# keyboard.net
KiCad netlist of a schematic drawn in EasyEDA Pro
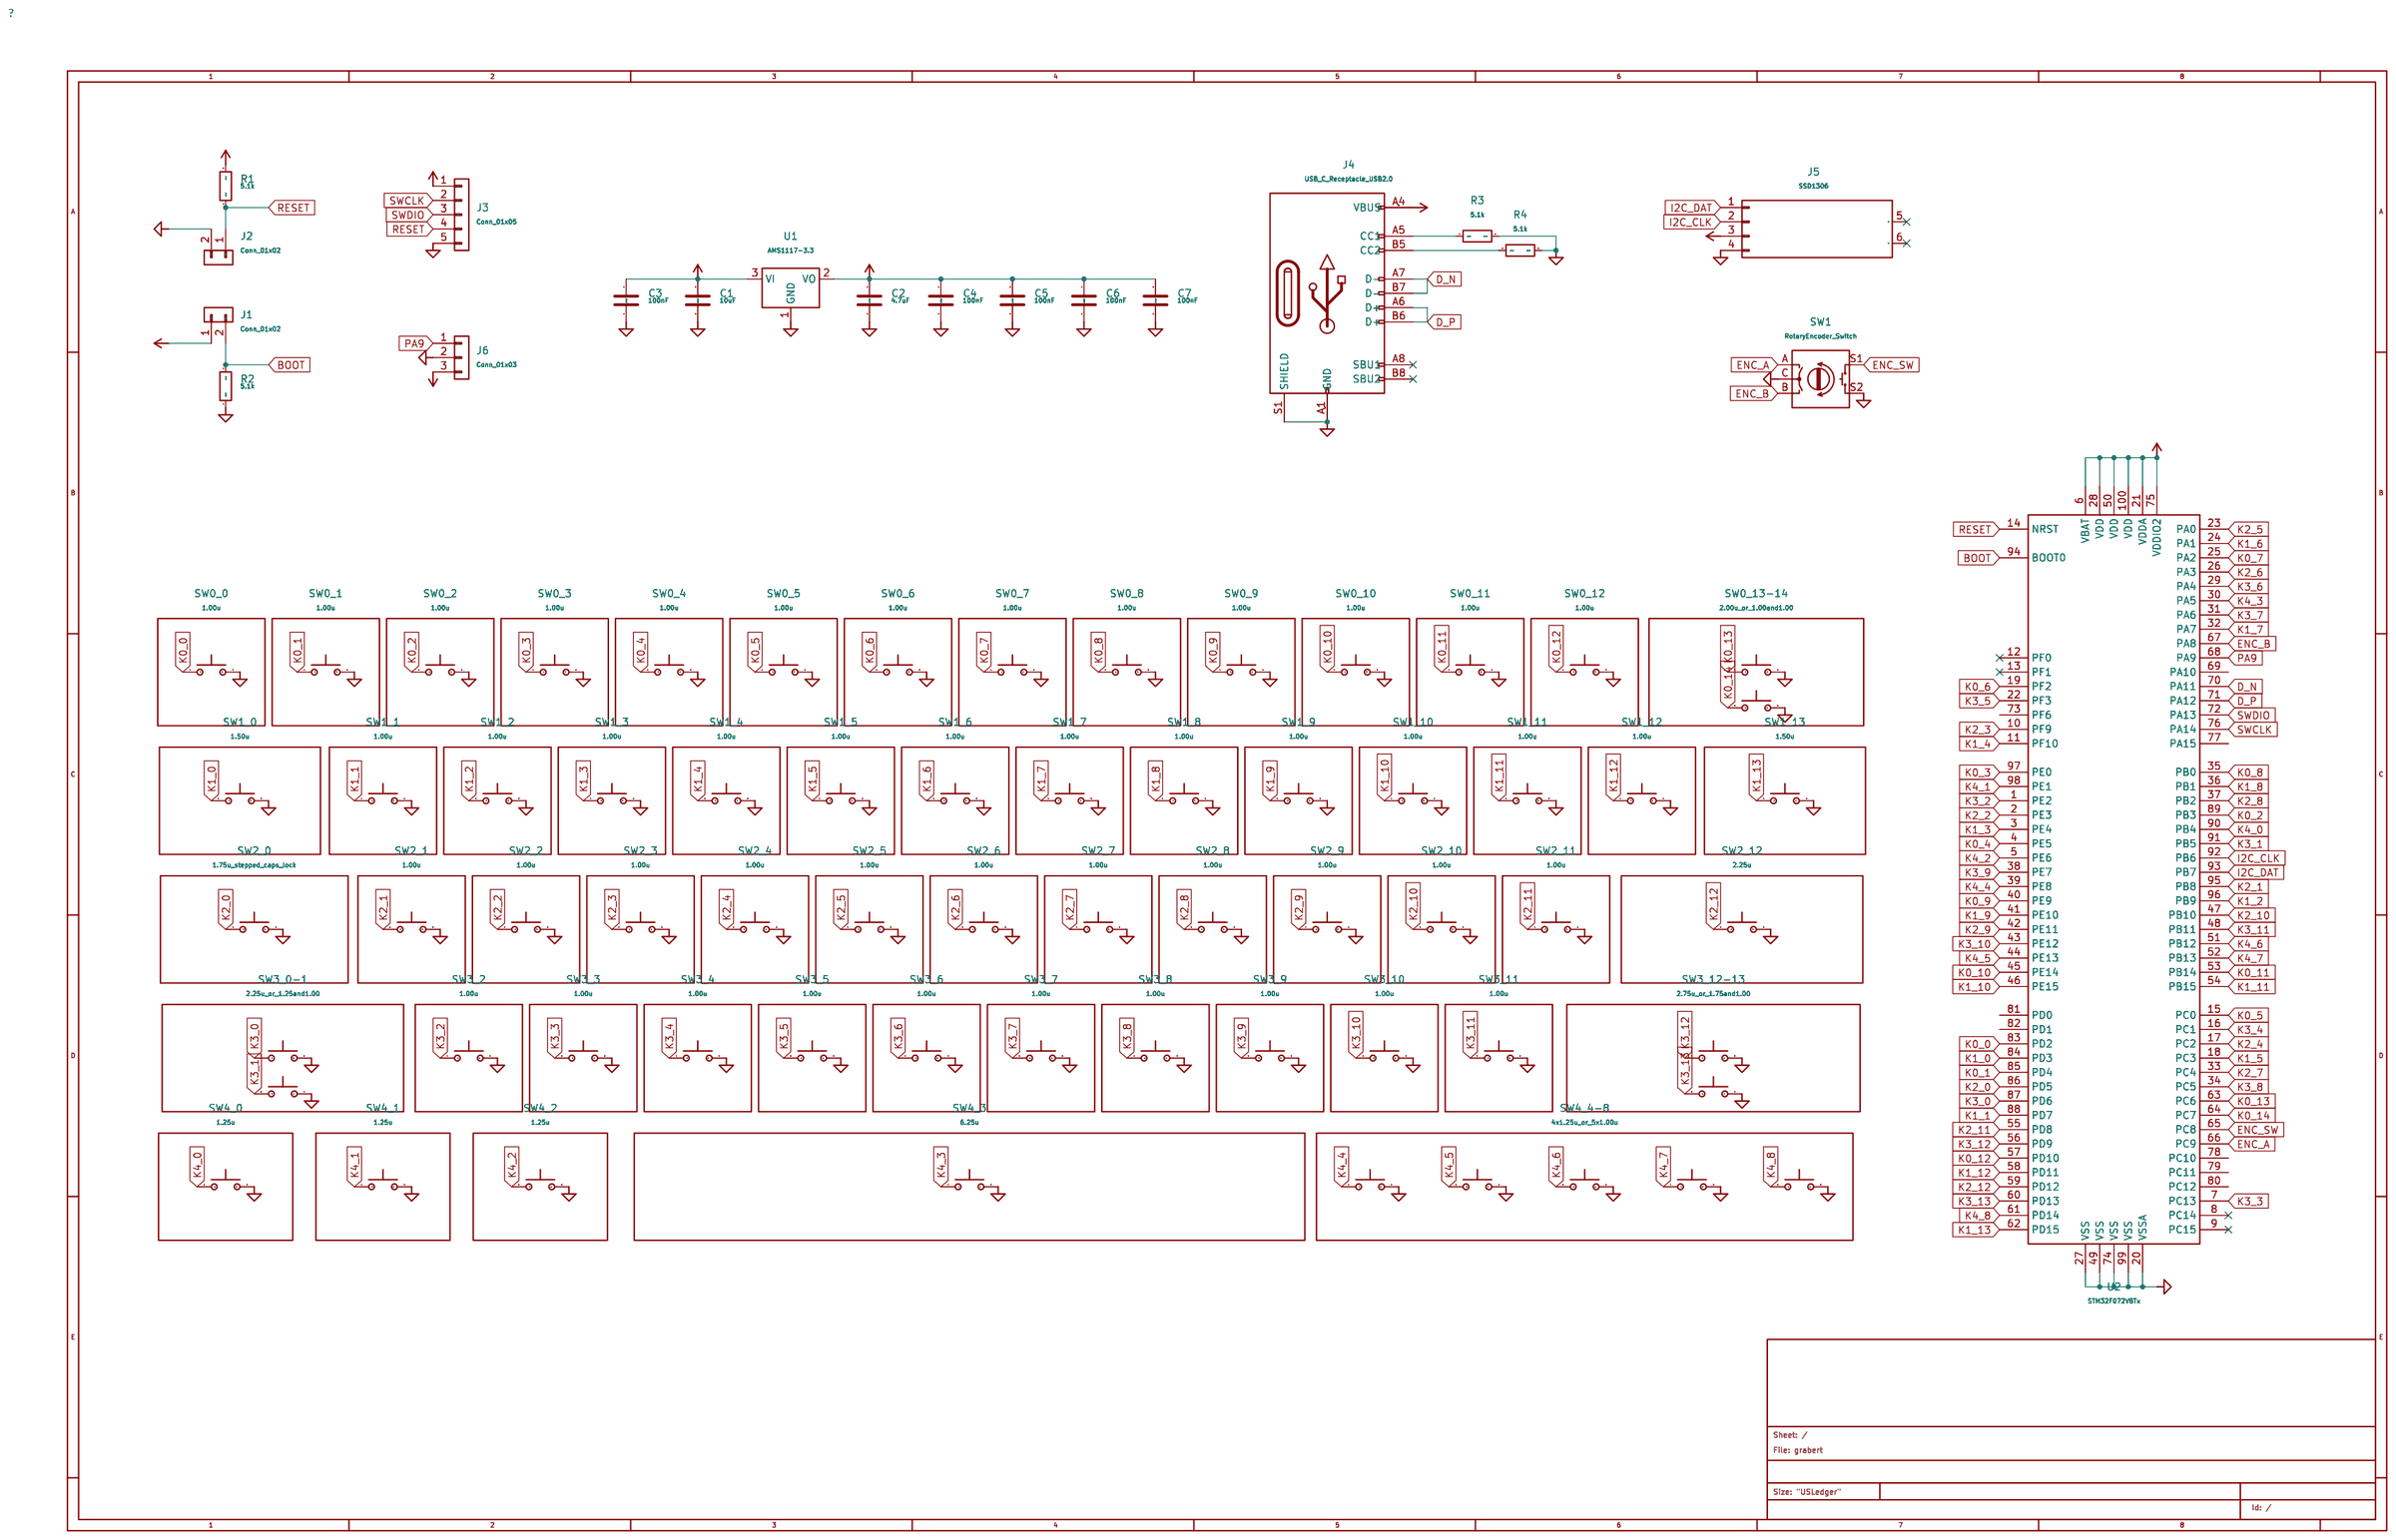
[diagram p0: schematic sheet]

(export (version "E")
  (design (tool "Eeschema 10.0.6"))
  (components
    (comp (ref "C1") (value "10uF") (libsource (lib "easyedapro") (part "Device_C")))
    (comp (ref "C2") (value "4.7uF") (libsource (lib "easyedapro") (part "Device_C")))
    (comp (ref "C3") (value "100nF") (libsource (lib "easyedapro") (part "Device_C")))
    (comp (ref "C4") (value "100nF") (libsource (lib "easyedapro") (part "Device_C")))
    (comp (ref "C5") (value "100nF") (libsource (lib "easyedapro") (part "Device_C")))
    (comp (ref "C6") (value "100nF") (libsource (lib "easyedapro") (part "Device_C")))
    (comp (ref "C7") (value "100nF") (libsource (lib "easyedapro") (part "Device_C")))
    (comp (ref "J1")
      (value "Conn_01x02")
      (libsource (lib "easyedapro") (part "Connector_Generic_Conn_01x02"))
    )
    (comp (ref "J2")
      (value "Conn_01x02")
      (libsource (lib "easyedapro") (part "Connector_Generic_Conn_01x02"))
    )
    (comp (ref "J3")
      (value "Conn_01x05")
      (libsource (lib "easyedapro") (part "Connector_Generic_Conn_01x05"))
    )
    (comp (ref "J4")
      (value "USB_C_Receptacle_USB2.0")
      (libsource (lib "easyedapro") (part "Connector_USB_C_Receptacle_USB2.0"))
    )
    (comp (ref "J5") (value "SSD1306") (libsource (lib "easyedapro") (part "kobuss_SSD1306")))
    (comp (ref "J6")
      (value "Conn_01x03")
      (libsource (lib "easyedapro") (part "Connector_Generic_Conn_01x03"))
    )
    (comp (ref "R1") (value "5.1k") (libsource (lib "easyedapro") (part "Device_R")))
    (comp (ref "R2") (value "5.1k") (libsource (lib "easyedapro") (part "Device_R")))
    (comp (ref "R3") (value "5.1k") (libsource (lib "easyedapro") (part "Device_R")))
    (comp (ref "R4") (value "5.1k") (libsource (lib "easyedapro") (part "Device_R")))
    (comp (ref "SW0_0") (value "1.00u") (libsource (lib "easyedapro") (part "kobuss_1.00u")))
    (comp (ref "SW0_1") (value "1.00u") (libsource (lib "easyedapro") (part "kobuss_1.00u")))
    (comp (ref "SW0_2") (value "1.00u") (libsource (lib "easyedapro") (part "kobuss_1.00u")))
    (comp (ref "SW0_3") (value "1.00u") (libsource (lib "easyedapro") (part "kobuss_1.00u")))
    (comp (ref "SW0_4") (value "1.00u") (libsource (lib "easyedapro") (part "kobuss_1.00u")))
    (comp (ref "SW0_5") (value "1.00u") (libsource (lib "easyedapro") (part "kobuss_1.00u")))
    (comp (ref "SW0_6") (value "1.00u") (libsource (lib "easyedapro") (part "kobuss_1.00u")))
    (comp (ref "SW0_7") (value "1.00u") (libsource (lib "easyedapro") (part "kobuss_1.00u")))
    (comp (ref "SW0_8") (value "1.00u") (libsource (lib "easyedapro") (part "kobuss_1.00u")))
    (comp (ref "SW0_9") (value "1.00u") (libsource (lib "easyedapro") (part "kobuss_1.00u")))
    (comp (ref "SW0_10") (value "1.00u") (libsource (lib "easyedapro") (part "kobuss_1.00u")))
    (comp (ref "SW0_11") (value "1.00u") (libsource (lib "easyedapro") (part "kobuss_1.00u")))
    (comp (ref "SW0_12") (value "1.00u") (libsource (lib "easyedapro") (part "kobuss_1.00u")))
    (comp (ref "SW0_13-14")
      (value "2.00u_or_1.00and1.00")
      (libsource (lib "easyedapro") (part "kobuss_2.00u_or_1.00and1.00"))
    )
    (comp (ref "SW1")
      (value "RotaryEncoder_Switch")
      (libsource (lib "easyedapro") (part "Device_RotaryEncoder_Switch"))
    )
    (comp (ref "SW1_0") (value "1.50u") (libsource (lib "easyedapro") (part "kobuss_1.50u")))
    (comp (ref "SW1_1") (value "1.00u") (libsource (lib "easyedapro") (part "kobuss_1.00u")))
    (comp (ref "SW1_2") (value "1.00u") (libsource (lib "easyedapro") (part "kobuss_1.00u")))
    (comp (ref "SW1_3") (value "1.00u") (libsource (lib "easyedapro") (part "kobuss_1.00u")))
    (comp (ref "SW1_4") (value "1.00u") (libsource (lib "easyedapro") (part "kobuss_1.00u")))
    (comp (ref "SW1_5") (value "1.00u") (libsource (lib "easyedapro") (part "kobuss_1.00u")))
    (comp (ref "SW1_6") (value "1.00u") (libsource (lib "easyedapro") (part "kobuss_1.00u")))
    (comp (ref "SW1_7") (value "1.00u") (libsource (lib "easyedapro") (part "kobuss_1.00u")))
    (comp (ref "SW1_8") (value "1.00u") (libsource (lib "easyedapro") (part "kobuss_1.00u")))
    (comp (ref "SW1_9") (value "1.00u") (libsource (lib "easyedapro") (part "kobuss_1.00u")))
    (comp (ref "SW1_10") (value "1.00u") (libsource (lib "easyedapro") (part "kobuss_1.00u")))
    (comp (ref "SW1_11") (value "1.00u") (libsource (lib "easyedapro") (part "kobuss_1.00u")))
    (comp (ref "SW1_12") (value "1.00u") (libsource (lib "easyedapro") (part "kobuss_1.00u")))
    (comp (ref "SW1_13") (value "1.50u") (libsource (lib "easyedapro") (part "kobuss_1.50u")))
    (comp (ref "SW2_0")
      (value "1.75u_stepped_caps_lock")
      (libsource (lib "easyedapro") (part "kobuss_1.75u_stepped_caps_lock"))
    )
    (comp (ref "SW2_1") (value "1.00u") (libsource (lib "easyedapro") (part "kobuss_1.00u")))
    (comp (ref "SW2_2") (value "1.00u") (libsource (lib "easyedapro") (part "kobuss_1.00u")))
    (comp (ref "SW2_3") (value "1.00u") (libsource (lib "easyedapro") (part "kobuss_1.00u")))
    (comp (ref "SW2_4") (value "1.00u") (libsource (lib "easyedapro") (part "kobuss_1.00u")))
    (comp (ref "SW2_5") (value "1.00u") (libsource (lib "easyedapro") (part "kobuss_1.00u")))
    (comp (ref "SW2_6") (value "1.00u") (libsource (lib "easyedapro") (part "kobuss_1.00u")))
    (comp (ref "SW2_7") (value "1.00u") (libsource (lib "easyedapro") (part "kobuss_1.00u")))
    (comp (ref "SW2_8") (value "1.00u") (libsource (lib "easyedapro") (part "kobuss_1.00u")))
    (comp (ref "SW2_9") (value "1.00u") (libsource (lib "easyedapro") (part "kobuss_1.00u")))
    (comp (ref "SW2_10") (value "1.00u") (libsource (lib "easyedapro") (part "kobuss_1.00u")))
    (comp (ref "SW2_11") (value "1.00u") (libsource (lib "easyedapro") (part "kobuss_1.00u")))
    (comp (ref "SW2_12") (value "2.25u") (libsource (lib "easyedapro") (part "kobuss_2.25u")))
    (comp (ref "SW3_0-1")
      (value "2.25u_or_1.25and1.00")
      (libsource (lib "easyedapro") (part "kobuss_2.25u_or_1.25and1.00"))
    )
    (comp (ref "SW3_2") (value "1.00u") (libsource (lib "easyedapro") (part "kobuss_1.00u")))
    (comp (ref "SW3_3") (value "1.00u") (libsource (lib "easyedapro") (part "kobuss_1.00u")))
    (comp (ref "SW3_4") (value "1.00u") (libsource (lib "easyedapro") (part "kobuss_1.00u")))
    (comp (ref "SW3_5") (value "1.00u") (libsource (lib "easyedapro") (part "kobuss_1.00u")))
    (comp (ref "SW3_6") (value "1.00u") (libsource (lib "easyedapro") (part "kobuss_1.00u")))
    (comp (ref "SW3_7") (value "1.00u") (libsource (lib "easyedapro") (part "kobuss_1.00u")))
    (comp (ref "SW3_8") (value "1.00u") (libsource (lib "easyedapro") (part "kobuss_1.00u")))
    (comp (ref "SW3_9") (value "1.00u") (libsource (lib "easyedapro") (part "kobuss_1.00u")))
    (comp (ref "SW3_10") (value "1.00u") (libsource (lib "easyedapro") (part "kobuss_1.00u")))
    (comp (ref "SW3_11") (value "1.00u") (libsource (lib "easyedapro") (part "kobuss_1.00u")))
    (comp (ref "SW3_12-13")
      (value "2.75u_or_1.75and1.00")
      (libsource (lib "easyedapro") (part "kobuss_2.75u_or_1.75and1.00"))
    )
    (comp (ref "SW4_0") (value "1.25u") (libsource (lib "easyedapro") (part "kobuss_1.25u")))
    (comp (ref "SW4_1") (value "1.25u") (libsource (lib "easyedapro") (part "kobuss_1.25u")))
    (comp (ref "SW4_2") (value "1.25u") (libsource (lib "easyedapro") (part "kobuss_1.25u")))
    (comp (ref "SW4_3") (value "6.25u") (libsource (lib "easyedapro") (part "kobuss_6.25u")))
    (comp (ref "SW4_4-8")
      (value "4x1.25u_or_5x1.00u")
      (libsource (lib "easyedapro") (part "kobuss_4x1.25u_or_5x1.00u"))
    )
    (comp (ref "U1")
      (value "AMS1117-3.3")
      (libsource (lib "easyedapro") (part "Regulator_Linear_AMS1117-3.3"))
    )
    (comp (ref "U2")
      (value "STM32F072V8Tx")
      (libsource (lib "easyedapro") (part "MCU_ST_STM32F0_STM32F072V8Tx"))
    )
  )
  (nets
    (net (code "1") (name "BOOT") (class "Default")
      (node (ref "J1") (pin "2") (pinfunction "Pin_2_2") (pintype "unspecified"))
      (node (ref "R2") (pin "2") (pinfunction "~_2") (pintype "unspecified"))
      (node (ref "U2") (pin "94") (pinfunction "BOOT0_94") (pintype "input"))
    )
    (net (code "2") (name "D_N") (class "Default")
      (node (ref "J4") (pin "A7") (pinfunction "D-_A7") (pintype "bidirectional"))
      (node (ref "J4") (pin "B7") (pinfunction "D-_B7") (pintype "bidirectional"))
      (node (ref "U2") (pin "70") (pinfunction "PA11_70") (pintype "bidirectional"))
    )
    (net (code "3") (name "D_P") (class "Default")
      (node (ref "J4") (pin "A6") (pinfunction "D+_A6") (pintype "bidirectional"))
      (node (ref "J4") (pin "B6") (pinfunction "D+_B6") (pintype "bidirectional"))
      (node (ref "U2") (pin "71") (pinfunction "PA12_71") (pintype "bidirectional"))
    )
    (net (code "4") (name "ENC_A") (class "Default")
      (node (ref "SW1") (pin "A") (pinfunction "A_A") (pintype "unspecified"))
      (node (ref "U2") (pin "66") (pinfunction "PC9_66") (pintype "bidirectional"))
    )
    (net (code "5") (name "ENC_B") (class "Default")
      (node (ref "SW1") (pin "B") (pinfunction "B_B") (pintype "unspecified"))
      (node (ref "U2") (pin "67") (pinfunction "PA8_67") (pintype "bidirectional"))
    )
    (net (code "6") (name "ENC_SW") (class "Default")
      (node (ref "SW1") (pin "S1") (pinfunction "S1_S1") (pintype "unspecified"))
      (node (ref "U2") (pin "65") (pinfunction "PC8_65") (pintype "bidirectional"))
    )
    (net (code "7") (name "I2C_CLK") (class "Default")
      (node (ref "J5") (pin "2") (pinfunction "SCL_2") (pintype "unspecified"))
      (node (ref "U2") (pin "92") (pinfunction "PB6_92") (pintype "bidirectional"))
    )
    (net (code "8") (name "I2C_DAT") (class "Default")
      (node (ref "J5") (pin "1") (pinfunction "SDA_1") (pintype "unspecified"))
      (node (ref "U2") (pin "93") (pinfunction "PB7_93") (pintype "bidirectional"))
    )
    (net (code "9") (name "K0_0") (class "Default")
      (node (ref "SW0_0") (pin "1") (pinfunction "1_1") (pintype "unspecified"))
      (node (ref "U2") (pin "83") (pinfunction "PD2_83") (pintype "bidirectional"))
    )
    (net (code "10") (name "K0_1") (class "Default")
      (node (ref "SW0_1") (pin "1") (pinfunction "1_1") (pintype "unspecified"))
      (node (ref "U2") (pin "85") (pinfunction "PD4_85") (pintype "bidirectional"))
    )
    (net (code "11") (name "K0_2") (class "Default")
      (node (ref "SW0_2") (pin "1") (pinfunction "1_1") (pintype "unspecified"))
      (node (ref "U2") (pin "89") (pinfunction "PB3_89") (pintype "bidirectional"))
    )
    (net (code "12") (name "K0_3") (class "Default")
      (node (ref "SW0_3") (pin "1") (pinfunction "1_1") (pintype "unspecified"))
      (node (ref "U2") (pin "97") (pinfunction "PE0_97") (pintype "bidirectional"))
    )
    (net (code "13") (name "K0_4") (class "Default")
      (node (ref "SW0_4") (pin "1") (pinfunction "1_1") (pintype "unspecified"))
      (node (ref "U2") (pin "4") (pinfunction "PE5_4") (pintype "bidirectional"))
    )
    (net (code "14") (name "K0_5") (class "Default")
      (node (ref "SW0_5") (pin "1") (pinfunction "1_1") (pintype "unspecified"))
      (node (ref "U2") (pin "15") (pinfunction "PC0_15") (pintype "bidirectional"))
    )
    (net (code "15") (name "K0_6") (class "Default")
      (node (ref "SW0_6") (pin "1") (pinfunction "1_1") (pintype "unspecified"))
      (node (ref "U2") (pin "19") (pinfunction "PF2_19") (pintype "bidirectional"))
    )
    (net (code "16") (name "K0_7") (class "Default")
      (node (ref "SW0_7") (pin "1") (pinfunction "1_1") (pintype "unspecified"))
      (node (ref "U2") (pin "25") (pinfunction "PA2_25") (pintype "bidirectional"))
    )
    (net (code "17") (name "K0_8") (class "Default")
      (node (ref "SW0_8") (pin "1") (pinfunction "1_1") (pintype "unspecified"))
      (node (ref "U2") (pin "35") (pinfunction "PB0_35") (pintype "bidirectional"))
    )
    (net (code "18") (name "K0_9") (class "Default")
      (node (ref "SW0_9") (pin "1") (pinfunction "1_1") (pintype "unspecified"))
      (node (ref "U2") (pin "40") (pinfunction "PE9_40") (pintype "bidirectional"))
    )
    (net (code "19") (name "K0_10") (class "Default")
      (node (ref "SW0_10") (pin "1") (pinfunction "1_1") (pintype "unspecified"))
      (node (ref "U2") (pin "45") (pinfunction "PE14_45") (pintype "bidirectional"))
    )
    (net (code "20") (name "K0_11") (class "Default")
      (node (ref "SW0_11") (pin "1") (pinfunction "1_1") (pintype "unspecified"))
      (node (ref "U2") (pin "53") (pinfunction "PB14_53") (pintype "bidirectional"))
    )
    (net (code "21") (name "K0_12") (class "Default")
      (node (ref "SW0_12") (pin "1") (pinfunction "1_1") (pintype "unspecified"))
      (node (ref "U2") (pin "57") (pinfunction "PD10_57") (pintype "bidirectional"))
    )
    (net (code "22") (name "K0_13") (class "Default")
      (node (ref "SW0_13-14") (pin "1") (pinfunction "1_1") (pintype "unspecified"))
      (node (ref "U2") (pin "63") (pinfunction "PC6_63") (pintype "bidirectional"))
    )
    (net (code "23") (name "K0_14") (class "Default")
      (node (ref "SW0_13-14") (pin "3") (pinfunction "3_3") (pintype "unspecified"))
      (node (ref "U2") (pin "64") (pinfunction "PC7_64") (pintype "bidirectional"))
    )
    (net (code "24") (name "K1_0") (class "Default")
      (node (ref "SW1_0") (pin "1") (pinfunction "1_1") (pintype "unspecified"))
      (node (ref "U2") (pin "84") (pinfunction "PD3_84") (pintype "bidirectional"))
    )
    (net (code "25") (name "K1_1") (class "Default")
      (node (ref "SW1_1") (pin "1") (pinfunction "1_1") (pintype "unspecified"))
      (node (ref "U2") (pin "88") (pinfunction "PD7_88") (pintype "bidirectional"))
    )
    (net (code "26") (name "K1_2") (class "Default")
      (node (ref "SW1_2") (pin "1") (pinfunction "1_1") (pintype "unspecified"))
      (node (ref "U2") (pin "96") (pinfunction "PB9_96") (pintype "bidirectional"))
    )
    (net (code "27") (name "K1_3") (class "Default")
      (node (ref "SW1_3") (pin "1") (pinfunction "1_1") (pintype "unspecified"))
      (node (ref "U2") (pin "3") (pinfunction "PE4_3") (pintype "bidirectional"))
    )
    (net (code "28") (name "K1_4") (class "Default")
      (node (ref "SW1_4") (pin "1") (pinfunction "1_1") (pintype "unspecified"))
      (node (ref "U2") (pin "11") (pinfunction "PF10_11") (pintype "bidirectional"))
    )
    (net (code "29") (name "K1_5") (class "Default")
      (node (ref "SW1_5") (pin "1") (pinfunction "1_1") (pintype "unspecified"))
      (node (ref "U2") (pin "18") (pinfunction "PC3_18") (pintype "bidirectional"))
    )
    (net (code "30") (name "K1_6") (class "Default")
      (node (ref "SW1_6") (pin "1") (pinfunction "1_1") (pintype "unspecified"))
      (node (ref "U2") (pin "24") (pinfunction "PA1_24") (pintype "bidirectional"))
    )
    (net (code "31") (name "K1_7") (class "Default")
      (node (ref "SW1_7") (pin "1") (pinfunction "1_1") (pintype "unspecified"))
      (node (ref "U2") (pin "32") (pinfunction "PA7_32") (pintype "bidirectional"))
    )
    (net (code "32") (name "K1_8") (class "Default")
      (node (ref "SW1_8") (pin "1") (pinfunction "1_1") (pintype "unspecified"))
      (node (ref "U2") (pin "36") (pinfunction "PB1_36") (pintype "bidirectional"))
    )
    (net (code "33") (name "K1_9") (class "Default")
      (node (ref "SW1_9") (pin "1") (pinfunction "1_1") (pintype "unspecified"))
      (node (ref "U2") (pin "41") (pinfunction "PE10_41") (pintype "bidirectional"))
    )
    (net (code "34") (name "K1_10") (class "Default")
      (node (ref "SW1_10") (pin "1") (pinfunction "1_1") (pintype "unspecified"))
      (node (ref "U2") (pin "46") (pinfunction "PE15_46") (pintype "bidirectional"))
    )
    (net (code "35") (name "K1_11") (class "Default")
      (node (ref "SW1_11") (pin "1") (pinfunction "1_1") (pintype "unspecified"))
      (node (ref "U2") (pin "54") (pinfunction "PB15_54") (pintype "bidirectional"))
    )
    (net (code "36") (name "K1_12") (class "Default")
      (node (ref "SW1_12") (pin "1") (pinfunction "1_1") (pintype "unspecified"))
      (node (ref "U2") (pin "58") (pinfunction "PD11_58") (pintype "bidirectional"))
    )
    (net (code "37") (name "K1_13") (class "Default")
      (node (ref "SW1_13") (pin "1") (pinfunction "1_1") (pintype "unspecified"))
      (node (ref "U2") (pin "62") (pinfunction "PD15_62") (pintype "bidirectional"))
    )
    (net (code "38") (name "K2_0") (class "Default")
      (node (ref "SW2_0") (pin "1") (pinfunction "1_1") (pintype "unspecified"))
      (node (ref "U2") (pin "86") (pinfunction "PD5_86") (pintype "bidirectional"))
    )
    (net (code "39") (name "K2_1") (class "Default")
      (node (ref "SW2_1") (pin "1") (pinfunction "1_1") (pintype "unspecified"))
      (node (ref "U2") (pin "95") (pinfunction "PB8_95") (pintype "bidirectional"))
    )
    (net (code "40") (name "K2_2") (class "Default")
      (node (ref "SW2_2") (pin "1") (pinfunction "1_1") (pintype "unspecified"))
      (node (ref "U2") (pin "2") (pinfunction "PE3_2") (pintype "bidirectional"))
    )
    (net (code "41") (name "K2_3") (class "Default")
      (node (ref "SW2_3") (pin "1") (pinfunction "1_1") (pintype "unspecified"))
      (node (ref "U2") (pin "10") (pinfunction "PF9_10") (pintype "bidirectional"))
    )
    (net (code "42") (name "K2_4") (class "Default")
      (node (ref "SW2_4") (pin "1") (pinfunction "1_1") (pintype "unspecified"))
      (node (ref "U2") (pin "17") (pinfunction "PC2_17") (pintype "bidirectional"))
    )
    (net (code "43") (name "K2_5") (class "Default")
      (node (ref "SW2_5") (pin "1") (pinfunction "1_1") (pintype "unspecified"))
      (node (ref "U2") (pin "23") (pinfunction "PA0_23") (pintype "bidirectional"))
    )
    (net (code "44") (name "K2_6") (class "Default")
      (node (ref "SW2_6") (pin "1") (pinfunction "1_1") (pintype "unspecified"))
      (node (ref "U2") (pin "26") (pinfunction "PA3_26") (pintype "bidirectional"))
    )
    (net (code "45") (name "K2_7") (class "Default")
      (node (ref "SW2_7") (pin "1") (pinfunction "1_1") (pintype "unspecified"))
      (node (ref "U2") (pin "33") (pinfunction "PC4_33") (pintype "bidirectional"))
    )
    (net (code "46") (name "K2_8") (class "Default")
      (node (ref "SW2_8") (pin "1") (pinfunction "1_1") (pintype "unspecified"))
      (node (ref "U2") (pin "37") (pinfunction "PB2_37") (pintype "bidirectional"))
    )
    (net (code "47") (name "K2_9") (class "Default")
      (node (ref "SW2_9") (pin "1") (pinfunction "1_1") (pintype "unspecified"))
      (node (ref "U2") (pin "42") (pinfunction "PE11_42") (pintype "bidirectional"))
    )
    (net (code "48") (name "K2_10") (class "Default")
      (node (ref "SW2_10") (pin "1") (pinfunction "1_1") (pintype "unspecified"))
      (node (ref "U2") (pin "47") (pinfunction "PB10_47") (pintype "bidirectional"))
    )
    (net (code "49") (name "K2_11") (class "Default")
      (node (ref "SW2_11") (pin "1") (pinfunction "1_1") (pintype "unspecified"))
      (node (ref "U2") (pin "55") (pinfunction "PD8_55") (pintype "bidirectional"))
    )
    (net (code "50") (name "K2_12") (class "Default")
      (node (ref "SW2_12") (pin "1") (pinfunction "1_1") (pintype "unspecified"))
      (node (ref "U2") (pin "59") (pinfunction "PD12_59") (pintype "bidirectional"))
    )
    (net (code "51") (name "K3_0") (class "Default")
      (node (ref "SW3_0-1") (pin "1") (pinfunction "1_1") (pintype "unspecified"))
      (node (ref "U2") (pin "87") (pinfunction "PD6_87") (pintype "bidirectional"))
    )
    (net (code "52") (name "K3_1") (class "Default")
      (node (ref "SW3_0-1") (pin "3") (pinfunction "3_3") (pintype "unspecified"))
      (node (ref "U2") (pin "91") (pinfunction "PB5_91") (pintype "bidirectional"))
    )
    (net (code "53") (name "K3_2") (class "Default")
      (node (ref "SW3_2") (pin "1") (pinfunction "1_1") (pintype "unspecified"))
      (node (ref "U2") (pin "1") (pinfunction "PE2_1") (pintype "bidirectional"))
    )
    (net (code "54") (name "K3_3") (class "Default")
      (node (ref "SW3_3") (pin "1") (pinfunction "1_1") (pintype "unspecified"))
      (node (ref "U2") (pin "7") (pinfunction "PC13_7") (pintype "bidirectional"))
    )
    (net (code "55") (name "K3_4") (class "Default")
      (node (ref "SW3_4") (pin "1") (pinfunction "1_1") (pintype "unspecified"))
      (node (ref "U2") (pin "16") (pinfunction "PC1_16") (pintype "bidirectional"))
    )
    (net (code "56") (name "K3_5") (class "Default")
      (node (ref "SW3_5") (pin "1") (pinfunction "1_1") (pintype "unspecified"))
      (node (ref "U2") (pin "22") (pinfunction "PF3_22") (pintype "bidirectional"))
    )
    (net (code "57") (name "K3_6") (class "Default")
      (node (ref "SW3_6") (pin "1") (pinfunction "1_1") (pintype "unspecified"))
      (node (ref "U2") (pin "29") (pinfunction "PA4_29") (pintype "bidirectional"))
    )
    (net (code "58") (name "K3_7") (class "Default")
      (node (ref "SW3_7") (pin "1") (pinfunction "1_1") (pintype "unspecified"))
      (node (ref "U2") (pin "31") (pinfunction "PA6_31") (pintype "bidirectional"))
    )
    (net (code "59") (name "K3_8") (class "Default")
      (node (ref "SW3_8") (pin "1") (pinfunction "1_1") (pintype "unspecified"))
      (node (ref "U2") (pin "34") (pinfunction "PC5_34") (pintype "bidirectional"))
    )
    (net (code "60") (name "K3_9") (class "Default")
      (node (ref "SW3_9") (pin "1") (pinfunction "1_1") (pintype "unspecified"))
      (node (ref "U2") (pin "38") (pinfunction "PE7_38") (pintype "bidirectional"))
    )
    (net (code "61") (name "K3_10") (class "Default")
      (node (ref "SW3_10") (pin "1") (pinfunction "1_1") (pintype "unspecified"))
      (node (ref "U2") (pin "43") (pinfunction "PE12_43") (pintype "bidirectional"))
    )
    (net (code "62") (name "K3_11") (class "Default")
      (node (ref "SW3_11") (pin "1") (pinfunction "1_1") (pintype "unspecified"))
      (node (ref "U2") (pin "48") (pinfunction "PB11_48") (pintype "bidirectional"))
    )
    (net (code "63") (name "K3_12") (class "Default")
      (node (ref "SW3_12-13") (pin "1") (pinfunction "1_1") (pintype "unspecified"))
      (node (ref "U2") (pin "56") (pinfunction "PD9_56") (pintype "bidirectional"))
    )
    (net (code "64") (name "K3_13") (class "Default")
      (node (ref "SW3_12-13") (pin "3") (pinfunction "3_3") (pintype "unspecified"))
      (node (ref "U2") (pin "60") (pinfunction "PD13_60") (pintype "bidirectional"))
    )
    (net (code "65") (name "K4_0") (class "Default")
      (node (ref "SW4_0") (pin "1") (pinfunction "1_1") (pintype "unspecified"))
      (node (ref "U2") (pin "90") (pinfunction "PB4_90") (pintype "bidirectional"))
    )
    (net (code "66") (name "K4_1") (class "Default")
      (node (ref "SW4_1") (pin "1") (pinfunction "1_1") (pintype "unspecified"))
      (node (ref "U2") (pin "98") (pinfunction "PE1_98") (pintype "bidirectional"))
    )
    (net (code "67") (name "K4_2") (class "Default")
      (node (ref "SW4_2") (pin "1") (pinfunction "1_1") (pintype "unspecified"))
      (node (ref "U2") (pin "5") (pinfunction "PE6_5") (pintype "bidirectional"))
    )
    (net (code "68") (name "K4_3") (class "Default")
      (node (ref "SW4_3") (pin "1") (pinfunction "1_1") (pintype "unspecified"))
      (node (ref "U2") (pin "30") (pinfunction "PA5_30") (pintype "bidirectional"))
    )
    (net (code "69") (name "K4_4") (class "Default")
      (node (ref "SW4_4-8") (pin "1") (pinfunction "1_1") (pintype "unspecified"))
      (node (ref "U2") (pin "39") (pinfunction "PE8_39") (pintype "bidirectional"))
    )
    (net (code "70") (name "K4_5") (class "Default")
      (node (ref "SW4_4-8") (pin "3") (pinfunction "3_3") (pintype "unspecified"))
      (node (ref "U2") (pin "44") (pinfunction "PE13_44") (pintype "bidirectional"))
    )
    (net (code "71") (name "K4_6") (class "Default")
      (node (ref "SW4_4-8") (pin "5") (pinfunction "5_5") (pintype "unspecified"))
      (node (ref "U2") (pin "51") (pinfunction "PB12_51") (pintype "bidirectional"))
    )
    (net (code "72") (name "K4_7") (class "Default")
      (node (ref "SW4_4-8") (pin "7") (pinfunction "7_7") (pintype "unspecified"))
      (node (ref "U2") (pin "52") (pinfunction "PB13_52") (pintype "bidirectional"))
    )
    (net (code "73") (name "K4_8") (class "Default")
      (node (ref "SW4_4-8") (pin "9") (pinfunction "9_9") (pintype "unspecified"))
      (node (ref "U2") (pin "61") (pinfunction "PD14_61") (pintype "bidirectional"))
    )
    (net (code "74") (name "Net-(J4-CC1)") (class "Default")
      (node (ref "J4") (pin "A5") (pinfunction "CC1_A5") (pintype "bidirectional"))
      (node (ref "R3") (pin "1") (pinfunction "~_1") (pintype "unspecified"))
    )
    (net (code "75") (name "Net-(J4-CC2)") (class "Default")
      (node (ref "J4") (pin "B5") (pinfunction "CC2_B5") (pintype "bidirectional"))
      (node (ref "R4") (pin "1") (pinfunction "~_1") (pintype "unspecified"))
    )
    (net (code "76") (name "PA9") (class "Default")
      (node (ref "J6") (pin "1") (pinfunction "Pin_1_1") (pintype "unspecified"))
      (node (ref "U2") (pin "68") (pinfunction "PA9_68") (pintype "bidirectional"))
    )
    (net (code "77") (name "POWER_+3V3") (class "Default")
      (node (ref "C2") (pin "1") (pinfunction "~_1") (pintype "unspecified"))
      (node (ref "C4") (pin "1") (pinfunction "~_1") (pintype "unspecified"))
      (node (ref "C5") (pin "1") (pinfunction "~_1") (pintype "unspecified"))
      (node (ref "C6") (pin "1") (pinfunction "~_1") (pintype "unspecified"))
      (node (ref "C7") (pin "1") (pinfunction "~_1") (pintype "unspecified"))
      (node (ref "J1") (pin "1") (pinfunction "Pin_1_1") (pintype "unspecified"))
      (node (ref "J3") (pin "1") (pinfunction "Pin_1_1") (pintype "unspecified"))
      (node (ref "J5") (pin "3") (pinfunction "VCC_3") (pintype "unspecified"))
      (node (ref "R1") (pin "2") (pinfunction "~_2") (pintype "unspecified"))
      (node (ref "U1") (pin "2") (pinfunction "VO_2") (pintype "unspecified"))
      (node (ref "U2") (pin "100") (pinfunction "VDD_100") (pintype "unspecified"))
      (node (ref "U2") (pin "21") (pinfunction "VDDA_21") (pintype "unspecified"))
      (node (ref "U2") (pin "28") (pinfunction "VDD_28") (pintype "unspecified"))
      (node (ref "U2") (pin "50") (pinfunction "VDD_50") (pintype "unspecified"))
      (node (ref "U2") (pin "6") (pinfunction "VBAT_6") (pintype "unspecified"))
      (node (ref "U2") (pin "75") (pinfunction "VDDIO2_75") (pintype "unspecified"))
    )
    (net (code "78") (name "POWER_+5V") (class "Default")
      (node (ref "C1") (pin "1") (pinfunction "~_1") (pintype "unspecified"))
      (node (ref "C3") (pin "1") (pinfunction "~_1") (pintype "unspecified"))
      (node (ref "J4") (pin "A4") (pinfunction "VBUS_A4") (pintype "unspecified"))
      (node (ref "J4") (pin "A9") (pinfunction "VBUS_A9") (pintype "unspecified"))
      (node (ref "J4") (pin "B4") (pinfunction "VBUS_B4") (pintype "unspecified"))
      (node (ref "J4") (pin "B9") (pinfunction "VBUS_B9") (pintype "unspecified"))
      (node (ref "J6") (pin "3") (pinfunction "Pin_3_3") (pintype "unspecified"))
      (node (ref "U1") (pin "3") (pinfunction "VI_3") (pintype "unspecified"))
    )
    (net (code "79") (name "POWER_GND") (class "Default")
      (node (ref "C1") (pin "2") (pinfunction "~_2") (pintype "unspecified"))
      (node (ref "C2") (pin "2") (pinfunction "~_2") (pintype "unspecified"))
      (node (ref "C3") (pin "2") (pinfunction "~_2") (pintype "unspecified"))
      (node (ref "C4") (pin "2") (pinfunction "~_2") (pintype "unspecified"))
      (node (ref "C5") (pin "2") (pinfunction "~_2") (pintype "unspecified"))
      (node (ref "C6") (pin "2") (pinfunction "~_2") (pintype "unspecified"))
      (node (ref "C7") (pin "2") (pinfunction "~_2") (pintype "unspecified"))
      (node (ref "J2") (pin "2") (pinfunction "Pin_2_2") (pintype "unspecified"))
      (node (ref "J3") (pin "5") (pinfunction "Pin_5_5") (pintype "unspecified"))
      (node (ref "J4") (pin "A1") (pinfunction "GND_A1") (pintype "unspecified"))
      (node (ref "J4") (pin "A12") (pinfunction "GND_A12") (pintype "unspecified"))
      (node (ref "J4") (pin "B1") (pinfunction "GND_B1") (pintype "unspecified"))
      (node (ref "J4") (pin "B12") (pinfunction "GND_B12") (pintype "unspecified"))
      (node (ref "J4") (pin "S1") (pinfunction "SHIELD_S1") (pintype "unspecified"))
      (node (ref "J5") (pin "4") (pinfunction "GND_4") (pintype "unspecified"))
      (node (ref "J6") (pin "2") (pinfunction "Pin_2_2") (pintype "unspecified"))
      (node (ref "R2") (pin "1") (pinfunction "~_1") (pintype "unspecified"))
      (node (ref "R3") (pin "2") (pinfunction "~_2") (pintype "unspecified"))
      (node (ref "R4") (pin "2") (pinfunction "~_2") (pintype "unspecified"))
      (node (ref "SW0_0") (pin "2") (pinfunction "2_2") (pintype "unspecified"))
      (node (ref "SW0_1") (pin "2") (pinfunction "2_2") (pintype "unspecified"))
      (node (ref "SW0_10") (pin "2") (pinfunction "2_2") (pintype "unspecified"))
      (node (ref "SW0_11") (pin "2") (pinfunction "2_2") (pintype "unspecified"))
      (node (ref "SW0_12") (pin "2") (pinfunction "2_2") (pintype "unspecified"))
      (node (ref "SW0_13-14") (pin "2") (pinfunction "2_2") (pintype "unspecified"))
      (node (ref "SW0_13-14") (pin "4") (pinfunction "4_4") (pintype "unspecified"))
      (node (ref "SW0_2") (pin "2") (pinfunction "2_2") (pintype "unspecified"))
      (node (ref "SW0_3") (pin "2") (pinfunction "2_2") (pintype "unspecified"))
      (node (ref "SW0_4") (pin "2") (pinfunction "2_2") (pintype "unspecified"))
      (node (ref "SW0_5") (pin "2") (pinfunction "2_2") (pintype "unspecified"))
      (node (ref "SW0_6") (pin "2") (pinfunction "2_2") (pintype "unspecified"))
      (node (ref "SW0_7") (pin "2") (pinfunction "2_2") (pintype "unspecified"))
      (node (ref "SW0_8") (pin "2") (pinfunction "2_2") (pintype "unspecified"))
      (node (ref "SW0_9") (pin "2") (pinfunction "2_2") (pintype "unspecified"))
      (node (ref "SW1") (pin "C") (pinfunction "C_C") (pintype "unspecified"))
      (node (ref "SW1") (pin "S2") (pinfunction "S2_S2") (pintype "unspecified"))
      (node (ref "SW1_0") (pin "2") (pinfunction "2_2") (pintype "unspecified"))
      (node (ref "SW1_1") (pin "2") (pinfunction "2_2") (pintype "unspecified"))
      (node (ref "SW1_10") (pin "2") (pinfunction "2_2") (pintype "unspecified"))
      (node (ref "SW1_11") (pin "2") (pinfunction "2_2") (pintype "unspecified"))
      (node (ref "SW1_12") (pin "2") (pinfunction "2_2") (pintype "unspecified"))
      (node (ref "SW1_13") (pin "2") (pinfunction "2_2") (pintype "unspecified"))
      (node (ref "SW1_2") (pin "2") (pinfunction "2_2") (pintype "unspecified"))
      (node (ref "SW1_3") (pin "2") (pinfunction "2_2") (pintype "unspecified"))
      (node (ref "SW1_4") (pin "2") (pinfunction "2_2") (pintype "unspecified"))
      (node (ref "SW1_5") (pin "2") (pinfunction "2_2") (pintype "unspecified"))
      (node (ref "SW1_6") (pin "2") (pinfunction "2_2") (pintype "unspecified"))
      (node (ref "SW1_7") (pin "2") (pinfunction "2_2") (pintype "unspecified"))
      (node (ref "SW1_8") (pin "2") (pinfunction "2_2") (pintype "unspecified"))
      (node (ref "SW1_9") (pin "2") (pinfunction "2_2") (pintype "unspecified"))
      (node (ref "SW2_0") (pin "2") (pinfunction "2_2") (pintype "unspecified"))
      (node (ref "SW2_1") (pin "2") (pinfunction "2_2") (pintype "unspecified"))
      (node (ref "SW2_10") (pin "2") (pinfunction "2_2") (pintype "unspecified"))
      (node (ref "SW2_11") (pin "2") (pinfunction "2_2") (pintype "unspecified"))
      (node (ref "SW2_12") (pin "2") (pinfunction "2_2") (pintype "unspecified"))
      (node (ref "SW2_2") (pin "2") (pinfunction "2_2") (pintype "unspecified"))
      (node (ref "SW2_3") (pin "2") (pinfunction "2_2") (pintype "unspecified"))
      (node (ref "SW2_4") (pin "2") (pinfunction "2_2") (pintype "unspecified"))
      (node (ref "SW2_5") (pin "2") (pinfunction "2_2") (pintype "unspecified"))
      (node (ref "SW2_6") (pin "2") (pinfunction "2_2") (pintype "unspecified"))
      (node (ref "SW2_7") (pin "2") (pinfunction "2_2") (pintype "unspecified"))
      (node (ref "SW2_8") (pin "2") (pinfunction "2_2") (pintype "unspecified"))
      (node (ref "SW2_9") (pin "2") (pinfunction "2_2") (pintype "unspecified"))
      (node (ref "SW3_0-1") (pin "2") (pinfunction "2_2") (pintype "unspecified"))
      (node (ref "SW3_0-1") (pin "4") (pinfunction "4_4") (pintype "unspecified"))
      (node (ref "SW3_10") (pin "2") (pinfunction "2_2") (pintype "unspecified"))
      (node (ref "SW3_11") (pin "2") (pinfunction "2_2") (pintype "unspecified"))
      (node (ref "SW3_12-13") (pin "2") (pinfunction "2_2") (pintype "unspecified"))
      (node (ref "SW3_12-13") (pin "4") (pinfunction "4_4") (pintype "unspecified"))
      (node (ref "SW3_2") (pin "2") (pinfunction "2_2") (pintype "unspecified"))
      (node (ref "SW3_3") (pin "2") (pinfunction "2_2") (pintype "unspecified"))
      (node (ref "SW3_4") (pin "2") (pinfunction "2_2") (pintype "unspecified"))
      (node (ref "SW3_5") (pin "2") (pinfunction "2_2") (pintype "unspecified"))
      (node (ref "SW3_6") (pin "2") (pinfunction "2_2") (pintype "unspecified"))
      (node (ref "SW3_7") (pin "2") (pinfunction "2_2") (pintype "unspecified"))
      (node (ref "SW3_8") (pin "2") (pinfunction "2_2") (pintype "unspecified"))
      (node (ref "SW3_9") (pin "2") (pinfunction "2_2") (pintype "unspecified"))
      (node (ref "SW4_0") (pin "2") (pinfunction "2_2") (pintype "unspecified"))
      (node (ref "SW4_1") (pin "2") (pinfunction "2_2") (pintype "unspecified"))
      (node (ref "SW4_2") (pin "2") (pinfunction "2_2") (pintype "unspecified"))
      (node (ref "SW4_3") (pin "2") (pinfunction "2_2") (pintype "unspecified"))
      (node (ref "SW4_4-8") (pin "10") (pinfunction "10_10") (pintype "unspecified"))
      (node (ref "SW4_4-8") (pin "2") (pinfunction "2_2") (pintype "unspecified"))
      (node (ref "SW4_4-8") (pin "4") (pinfunction "4_4") (pintype "unspecified"))
      (node (ref "SW4_4-8") (pin "6") (pinfunction "6_6") (pintype "unspecified"))
      (node (ref "SW4_4-8") (pin "8") (pinfunction "8_8") (pintype "unspecified"))
      (node (ref "U1") (pin "1") (pinfunction "GND_1") (pintype "unspecified"))
      (node (ref "U2") (pin "20") (pinfunction "VSSA_20") (pintype "unspecified"))
      (node (ref "U2") (pin "27") (pinfunction "VSS_27") (pintype "unspecified"))
      (node (ref "U2") (pin "49") (pinfunction "VSS_49") (pintype "unspecified"))
      (node (ref "U2") (pin "74") (pinfunction "VSS_74") (pintype "unspecified"))
      (node (ref "U2") (pin "99") (pinfunction "VSS_99") (pintype "unspecified"))
    )
    (net (code "80") (name "RESET") (class "Default")
      (node (ref "J2") (pin "1") (pinfunction "Pin_1_1") (pintype "unspecified"))
      (node (ref "J3") (pin "4") (pinfunction "Pin_4_4") (pintype "unspecified"))
      (node (ref "R1") (pin "1") (pinfunction "~_1") (pintype "unspecified"))
      (node (ref "U2") (pin "14") (pinfunction "NRST_14") (pintype "input"))
    )
    (net (code "81") (name "SWCLK") (class "Default")
      (node (ref "J3") (pin "2") (pinfunction "Pin_2_2") (pintype "unspecified"))
      (node (ref "U2") (pin "76") (pinfunction "PA14_76") (pintype "bidirectional"))
    )
    (net (code "82") (name "SWDIO") (class "Default")
      (node (ref "J3") (pin "3") (pinfunction "Pin_3_3") (pintype "unspecified"))
      (node (ref "U2") (pin "72") (pinfunction "PA13_72") (pintype "bidirectional"))
    )
    (net (code "83") (name "unconnected-(J4-SBU1-PadA8)") (class "Default")
      (node (ref "J4") (pin "A8") (pinfunction "SBU1_A8") (pintype "bidirectional+no_connect"))
    )
    (net (code "84") (name "unconnected-(J4-SBU2-PadB8)") (class "Default")
      (node (ref "J4") (pin "B8") (pinfunction "SBU2_B8") (pintype "bidirectional+no_connect"))
    )
    (net (code "85") (name "unconnected-(J5-MNT-Pad5)") (class "Default")
      (node (ref "J5") (pin "5") (pinfunction "MNT_5") (pintype "unspecified+no_connect"))
    )
    (net (code "86") (name "unconnected-(J5-MNT-Pad6)") (class "Default")
      (node (ref "J5") (pin "6") (pinfunction "MNT_6") (pintype "unspecified+no_connect"))
    )
    (net (code "87") (name "unconnected-(U2-PA10-Pad69)") (class "Default")
      (node (ref "U2") (pin "69") (pinfunction "PA10_69") (pintype "bidirectional"))
    )
    (net (code "88") (name "unconnected-(U2-PA15-Pad77)") (class "Default")
      (node (ref "U2") (pin "77") (pinfunction "PA15_77") (pintype "bidirectional"))
    )
    (net (code "89") (name "unconnected-(U2-PC10-Pad78)") (class "Default")
      (node (ref "U2") (pin "78") (pinfunction "PC10_78") (pintype "bidirectional"))
    )
    (net (code "90") (name "unconnected-(U2-PC11-Pad79)") (class "Default")
      (node (ref "U2") (pin "79") (pinfunction "PC11_79") (pintype "bidirectional"))
    )
    (net (code "91") (name "unconnected-(U2-PC12-Pad80)") (class "Default")
      (node (ref "U2") (pin "80") (pinfunction "PC12_80") (pintype "bidirectional"))
    )
    (net (code "92") (name "unconnected-(U2-PC14-Pad8)") (class "Default")
      (node (ref "U2") (pin "8") (pinfunction "PC14_8") (pintype "bidirectional+no_connect"))
    )
    (net (code "93") (name "unconnected-(U2-PC15-Pad9)") (class "Default")
      (node (ref "U2") (pin "9") (pinfunction "PC15_9") (pintype "bidirectional+no_connect"))
    )
    (net (code "94") (name "unconnected-(U2-PD0-Pad81)") (class "Default")
      (node (ref "U2") (pin "81") (pinfunction "PD0_81") (pintype "bidirectional"))
    )
    (net (code "95") (name "unconnected-(U2-PD1-Pad82)") (class "Default")
      (node (ref "U2") (pin "82") (pinfunction "PD1_82") (pintype "bidirectional"))
    )
    (net (code "96") (name "unconnected-(U2-PF0-Pad12)") (class "Default")
      (node (ref "U2") (pin "12") (pinfunction "PF0_12") (pintype "input+no_connect"))
    )
    (net (code "97") (name "unconnected-(U2-PF1-Pad13)") (class "Default")
      (node (ref "U2") (pin "13") (pinfunction "PF1_13") (pintype "input+no_connect"))
    )
    (net (code "98") (name "unconnected-(U2-PF6-Pad73)") (class "Default")
      (node (ref "U2") (pin "73") (pinfunction "PF6_73") (pintype "bidirectional"))
    )
  )
)
